# PCB_OnOnfre_SINGLE_BETA1_Solenoid.net
KiCad netlist of a schematic drawn in EAGLE
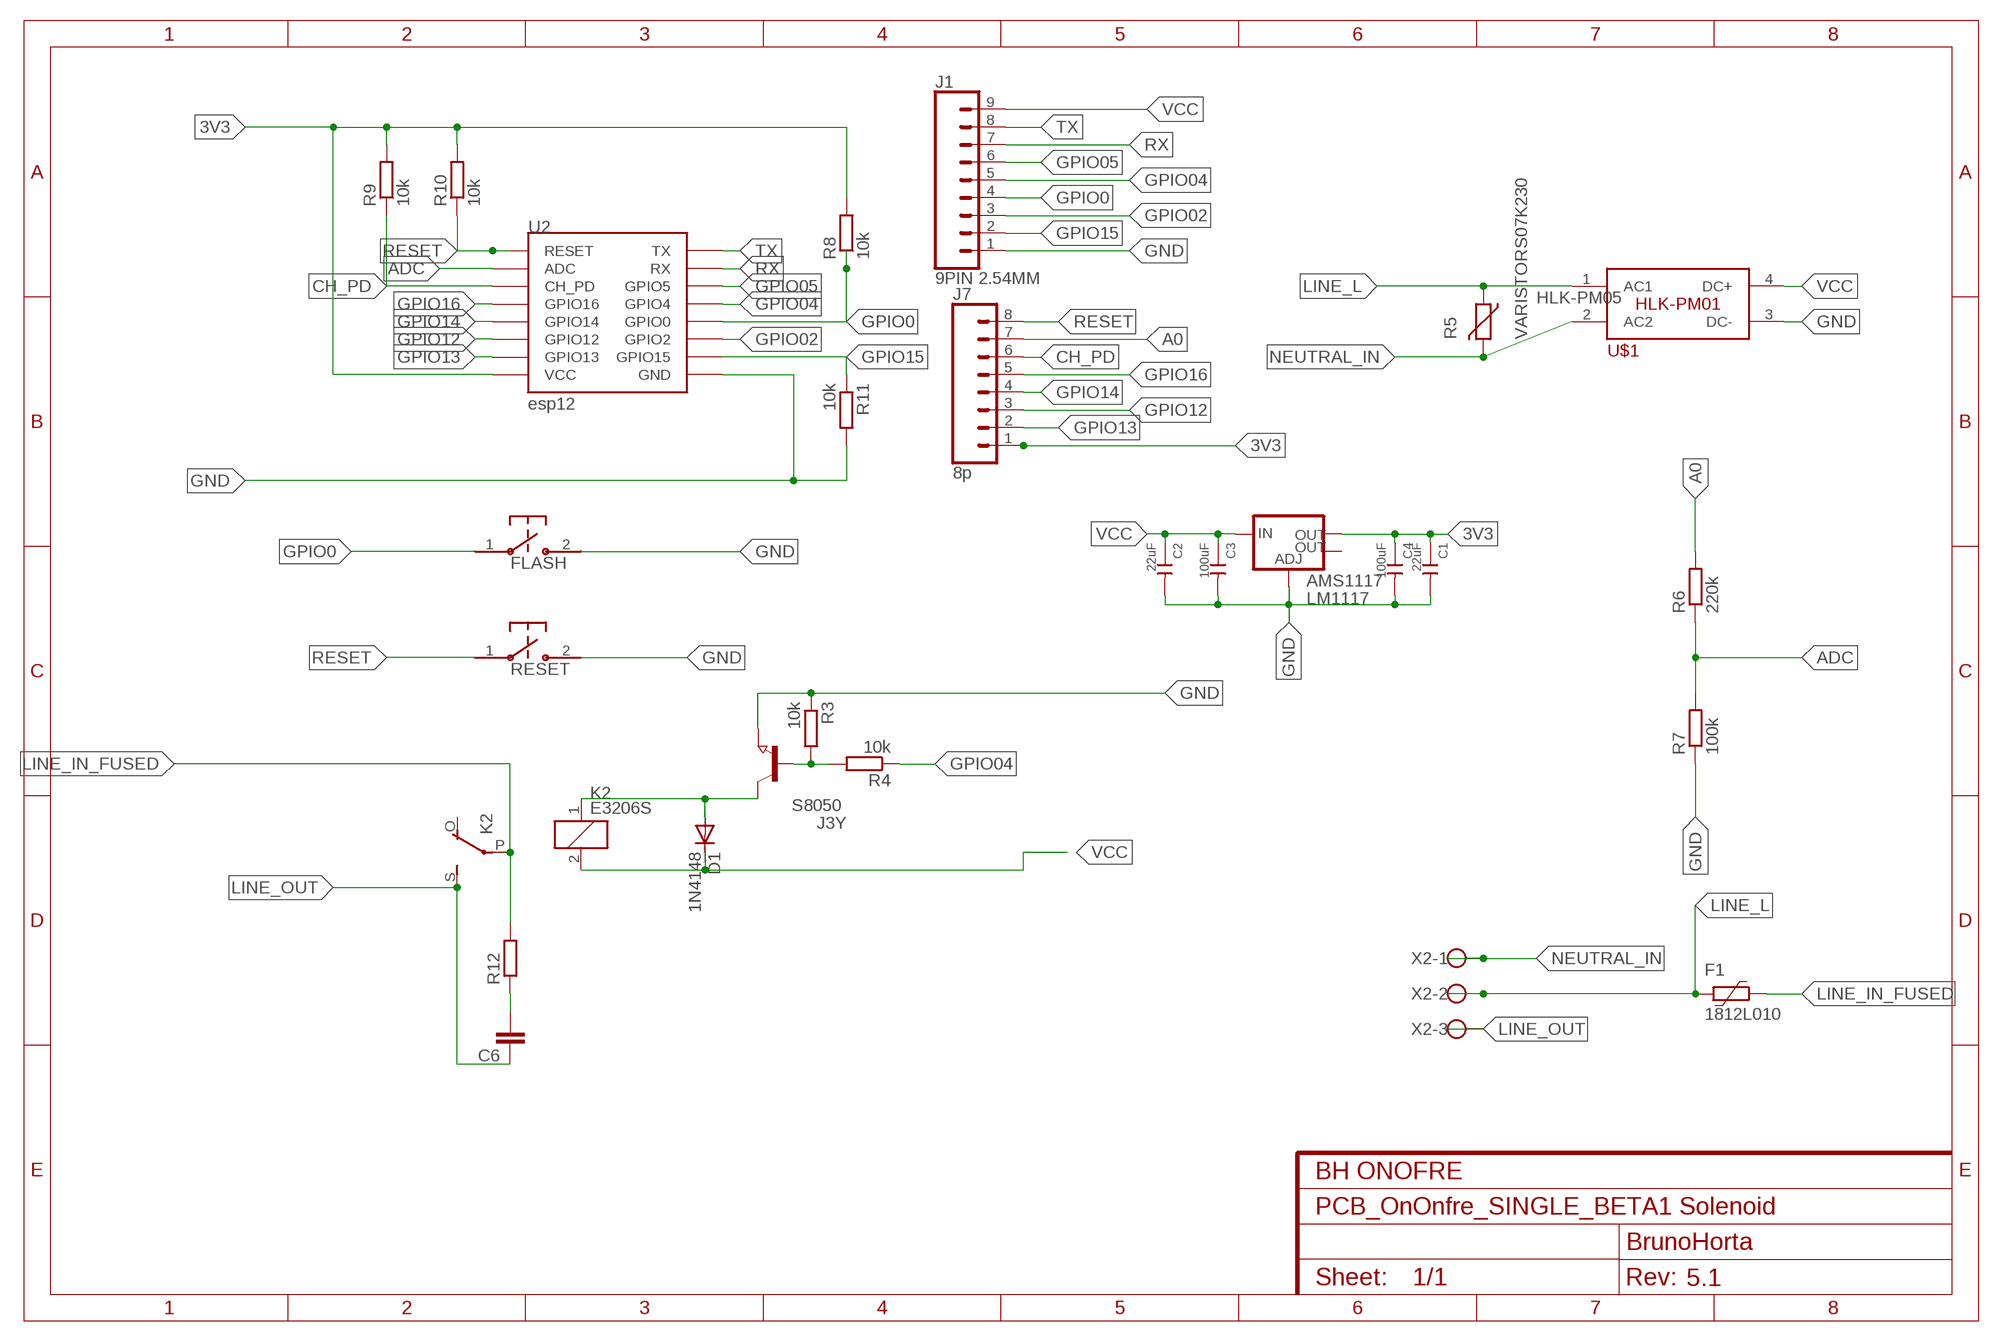
[diagram p0: schematic, sheet 1]

(export (version "E")
  (design (tool "Eeschema 10.0.6"))
  (components
    (comp (ref "AMS1117")
      (value "LM1117")
      (footprint "eagle-import:SOT223")
      (libsource (lib "eagle-import") (part "V_REG_LM1117SOT223"))
    )
    (comp (ref "C1")
      (value "22uF")
      (footprint "eagle-import:C1206")
      (fields (field (name "MPN") "CC1206KKX7RCBB102"))
      (libsource (lib "eagle-import") (part "CERAMIC-1NF-1KV-10%-X7R?(1206)"))
    )
    (comp (ref "C2")
      (value "22uF")
      (footprint "eagle-import:C1206")
      (fields (field (name "MPN") "CC1206KKX7RCBB102"))
      (libsource (lib "eagle-import") (part "CERAMIC-1NF-1KV-10%-X7R?(1206)"))
    )
    (comp (ref "C3")
      (value "100uF")
      (footprint "eagle-import:C1206")
      (fields (field (name "MPN") "CC1206KKX7RCBB102"))
      (libsource (lib "eagle-import") (part "CERAMIC-1NF-1KV-10%-X7R?(1206)"))
    )
    (comp (ref "C4")
      (value "100uF")
      (footprint "eagle-import:C1206")
      (fields (field (name "MPN") "CC1206KKX7RCBB102"))
      (libsource (lib "eagle-import") (part "CERAMIC-1NF-1KV-10%-X7R?(1206)"))
    )
    (comp (ref "C6")
      (value "C-EU102-043X133")
      (footprint "eagle-import:C102-043X133")
      (libsource (lib "eagle-import") (part "C-EU102-043X133"))
    )
    (comp (ref "D1")
      (value "1N4148")
      (footprint "eagle-import:SOD80C")
      (libsource (lib "eagle-import") (part "DIODE-SOD80C"))
    )
    (comp (ref "F1")
      (value "1812L010")
      (footprint "eagle-import:1812L")
      (fields (field (name "MF") "Littelfuse"))
      (libsource (lib "eagle-import") (part "?1812L010"))
    )
    (comp (ref "FLASH")
      (value "B3U-1000P-2P-SMD")
      (footprint "eagle-import:B3U-1000P")
      (fields (field (name "MANUFACTURER") "Omron") (field (name "MPN") "B3U-1000P"))
      (libsource (lib "eagle-import") (part "B3U-1000P"))
    )
    (comp (ref "J1")
      (value "9PIN 2.54MM")
      (footprint "eagle-import:1X09")
      (libsource (lib "eagle-import") (part "CONN_09"))
    )
    (comp (ref "J3Y")
      (value "S8050")
      (footprint "eagle-import:SOT23")
      (libsource (lib "eagle-import") (part "NPN-TRANSISTOR_SOT23"))
    )
    (comp (ref "J7")
      (value "8p")
      (footprint "eagle-import:1X08")
      (libsource (lib "eagle-import") (part "CONN_08{dblquote}"))
    )
    (comp (ref "K2")
      (value "E3206S")
      (footprint "eagle-import:E3206S")
      (libsource (lib "eagle-import") (part "E3206S"))
    )
    (comp (ref "R3")
      (value "10k")
      (footprint "eagle-import:R0603")
      (libsource (lib "eagle-import") (part "R-EU_R0603"))
    )
    (comp (ref "R4")
      (value "10k")
      (footprint "eagle-import:R0603")
      (libsource (lib "eagle-import") (part "R-EU_R0603"))
    )
    (comp (ref "R5")
      (value "VARISTORS07K230")
      (footprint "eagle-import:S07K230")
      (libsource (lib "eagle-import") (part "VARISTORS07K230"))
    )
    (comp (ref "R6")
      (value "220k")
      (footprint "eagle-import:R0603")
      (libsource (lib "eagle-import") (part "R-EU_R0603"))
    )
    (comp (ref "R7")
      (value "100k")
      (footprint "eagle-import:R0603")
      (libsource (lib "eagle-import") (part "R-EU_R0603"))
    )
    (comp (ref "R8")
      (value "10k")
      (footprint "eagle-import:R0603")
      (libsource (lib "eagle-import") (part "R-EU_R0603"))
    )
    (comp (ref "R9")
      (value "10k")
      (footprint "eagle-import:R0603")
      (libsource (lib "eagle-import") (part "R-EU_R0603"))
    )
    (comp (ref "R10")
      (value "10k")
      (footprint "eagle-import:R0603")
      (libsource (lib "eagle-import") (part "R-EU_R0603"))
    )
    (comp (ref "R11")
      (value "10k")
      (footprint "eagle-import:R0603")
      (libsource (lib "eagle-import") (part "R-EU_R0603"))
    )
    (comp (ref "R12")
      (value "R-EU_R2512")
      (footprint "eagle-import:R2512")
      (libsource (lib "eagle-import") (part "R-EU_R2512"))
    )
    (comp (ref "RESET")
      (value "B3U-1000P-2P-SMD")
      (footprint "eagle-import:B3U-1000P")
      (fields (field (name "MANUFACTURER") "Omron") (field (name "MPN") "B3U-1000P"))
      (libsource (lib "eagle-import") (part "B3U-1000P"))
    )
    (comp (ref "U$1")
      (value "HLK-PM01")
      (footprint "eagle-import:HLK-PM01")
      (fields (field (name "MF") "Hi-link") (field (name "MP") "hlk-pm01"))
      (libsource (lib "eagle-import") (part "HLK-PM01"))
    )
    (comp (ref "U2")
      (value "esp12")
      (footprint "eagle-import:ESP12-SMD")
      (libsource (lib "eagle-import") (part "ESP12SMD"))
    )
    (comp (ref "X2")
      (value "W237-103")
      (footprint "eagle-import:W237-103")
      (fields (field (name "MPN") "237-103"))
      (libsource (lib "eagle-import") (part "W237-103"))
    )
  )
  (nets
    (net (code "1") (name "3V3") (class "Default")
      (node (ref "AMS1117") (pin "2") (pinfunction "OUT_2") (pintype "output"))
      (node (ref "C1") (pin "1") (pinfunction "1_1") (pintype "passive"))
      (node (ref "C4") (pin "1") (pinfunction "1_1") (pintype "passive"))
      (node (ref "J7") (pin "1") (pinfunction "1_1") (pintype "passive"))
      (node (ref "R10") (pin "2") (pinfunction "2_2") (pintype "passive"))
      (node (ref "R8") (pin "2") (pinfunction "2_2") (pintype "passive"))
      (node (ref "R9") (pin "2") (pinfunction "2_2") (pintype "passive"))
      (node (ref "U2") (pin "VCC") (pinfunction "VCC_VCC") (pintype "bidirectional"))
    )
    (net (code "2") (name "A0") (class "Default")
      (node (ref "J7") (pin "7") (pinfunction "7_7") (pintype "passive"))
      (node (ref "R6") (pin "2") (pinfunction "2_2") (pintype "passive"))
    )
    (net (code "3") (name "ADC") (class "Default")
      (node (ref "R6") (pin "1") (pinfunction "1_1") (pintype "passive"))
      (node (ref "R7") (pin "2") (pinfunction "2_2") (pintype "passive"))
      (node (ref "U2") (pin "ADC") (pinfunction "ADC_ADC") (pintype "bidirectional"))
    )
    (net (code "4") (name "CH_PD") (class "Default")
      (node (ref "J7") (pin "6") (pinfunction "6_6") (pintype "passive"))
      (node (ref "R9") (pin "1") (pinfunction "1_1") (pintype "passive"))
      (node (ref "U2") (pin "CH_PD") (pinfunction "CH_PD_CH_PD") (pintype "bidirectional"))
    )
    (net (code "5") (name "GND") (class "Default")
      (node (ref "AMS1117") (pin "1") (pinfunction "ADJ_1") (pintype "input"))
      (node (ref "C1") (pin "2") (pinfunction "2_2") (pintype "passive"))
      (node (ref "C2") (pin "2") (pinfunction "2_2") (pintype "passive"))
      (node (ref "C3") (pin "2") (pinfunction "2_2") (pintype "passive"))
      (node (ref "C4") (pin "2") (pinfunction "2_2") (pintype "passive"))
      (node (ref "FLASH") (pin "2") (pinfunction "P$2_2") (pintype "passive"))
      (node (ref "J1") (pin "1") (pinfunction "1_1") (pintype "passive"))
      (node (ref "J3Y") (pin "2") (pinfunction "E_2") (pintype "passive"))
      (node (ref "R11") (pin "2") (pinfunction "2_2") (pintype "passive"))
      (node (ref "R3") (pin "1") (pinfunction "1_1") (pintype "passive"))
      (node (ref "R7") (pin "1") (pinfunction "1_1") (pintype "passive"))
      (node (ref "RESET") (pin "2") (pinfunction "P$2_2") (pintype "passive"))
      (node (ref "U$1") (pin "3") (pinfunction "DC-_3") (pintype "power_in"))
      (node (ref "U2") (pin "GND") (pinfunction "GND_GND") (pintype "bidirectional"))
    )
    (net (code "6") (name "GPIO0") (class "Default")
      (node (ref "FLASH") (pin "1") (pinfunction "P$1_1") (pintype "passive"))
      (node (ref "J1") (pin "4") (pinfunction "4_4") (pintype "passive"))
      (node (ref "R8") (pin "1") (pinfunction "1_1") (pintype "passive"))
      (node (ref "U2") (pin "GPIO0") (pinfunction "GPIO0_GPIO0") (pintype "bidirectional"))
    )
    (net (code "7") (name "GPIO02") (class "Default")
      (node (ref "J1") (pin "3") (pinfunction "3_3") (pintype "passive"))
      (node (ref "U2") (pin "GPIO2") (pinfunction "GPIO2_GPIO2") (pintype "bidirectional"))
    )
    (net (code "8") (name "GPIO04") (class "Default")
      (node (ref "J1") (pin "5") (pinfunction "5_5") (pintype "passive"))
      (node (ref "R4") (pin "1") (pinfunction "1_1") (pintype "passive"))
      (node (ref "U2") (pin "GPIO4") (pinfunction "GPIO4_GPIO4") (pintype "bidirectional"))
    )
    (net (code "9") (name "GPIO05") (class "Default")
      (node (ref "J1") (pin "6") (pinfunction "6_6") (pintype "passive"))
      (node (ref "U2") (pin "GPIO5") (pinfunction "GPIO5_GPIO5") (pintype "bidirectional"))
    )
    (net (code "10") (name "GPIO12") (class "Default")
      (node (ref "J7") (pin "3") (pinfunction "3_3") (pintype "passive"))
      (node (ref "U2") (pin "GPIO12") (pinfunction "GPIO12_GPIO12") (pintype "bidirectional"))
    )
    (net (code "11") (name "GPIO13") (class "Default")
      (node (ref "J7") (pin "2") (pinfunction "2_2") (pintype "passive"))
      (node (ref "U2") (pin "GPIO13") (pinfunction "GPIO13_GPIO13") (pintype "bidirectional"))
    )
    (net (code "12") (name "GPIO14") (class "Default")
      (node (ref "J7") (pin "4") (pinfunction "4_4") (pintype "passive"))
      (node (ref "U2") (pin "GPIO14") (pinfunction "GPIO14_GPIO14") (pintype "bidirectional"))
    )
    (net (code "13") (name "GPIO15") (class "Default")
      (node (ref "J1") (pin "2") (pinfunction "2_2") (pintype "passive"))
      (node (ref "R11") (pin "1") (pinfunction "1_1") (pintype "passive"))
      (node (ref "U2") (pin "GPIO15") (pinfunction "GPIO15_GPIO15") (pintype "bidirectional"))
    )
    (net (code "14") (name "GPIO16") (class "Default")
      (node (ref "J7") (pin "5") (pinfunction "5_5") (pintype "passive"))
      (node (ref "U2") (pin "GPIO16") (pinfunction "GPIO16_GPIO16") (pintype "bidirectional"))
    )
    (net (code "15") (name "LINE_IN_FUSED") (class "Default")
      (node (ref "F1") (pin "1") (pinfunction "1_1") (pintype "passive"))
      (node (ref "K2") (pin "P") (pinfunction "P_P") (pintype "passive"))
      (node (ref "R12") (pin "2") (pinfunction "2_2") (pintype "passive"))
    )
    (net (code "16") (name "LINE_L") (class "Default")
      (node (ref "F1") (pin "2") (pinfunction "2_2") (pintype "passive"))
      (node (ref "R5") (pin "1") (pinfunction "1_1") (pintype "passive"))
      (node (ref "U$1") (pin "1") (pinfunction "AC1_1") (pintype "power_in"))
      (node (ref "X2") (pin "2") (pinfunction "KL_2") (pintype "passive"))
    )
    (net (code "17") (name "LINE_OUT") (class "Default")
      (node (ref "C6") (pin "1") (pinfunction "1_1") (pintype "passive"))
      (node (ref "K2") (pin "S") (pinfunction "S_S") (pintype "passive"))
      (node (ref "X2") (pin "3") (pinfunction "KL_3") (pintype "passive"))
    )
    (net (code "18") (name "NEUTRAL_IN") (class "Default")
      (node (ref "R5") (pin "2") (pinfunction "2_2") (pintype "passive"))
      (node (ref "U$1") (pin "2") (pinfunction "AC2_2") (pintype "power_in"))
      (node (ref "X2") (pin "1") (pinfunction "KL_1") (pintype "passive"))
    )
    (net (code "19") (name "Net-(C6-Pad2)") (class "Default")
      (node (ref "C6") (pin "2") (pinfunction "2_2") (pintype "passive"))
      (node (ref "R12") (pin "1") (pinfunction "1_1") (pintype "passive"))
    )
    (net (code "20") (name "Net-(J3Y-B)") (class "Default")
      (node (ref "J3Y") (pin "1") (pinfunction "B_1") (pintype "passive"))
      (node (ref "R3") (pin "2") (pinfunction "2_2") (pintype "passive"))
      (node (ref "R4") (pin "2") (pinfunction "2_2") (pintype "passive"))
    )
    (net (code "21") (name "Net-(J3Y-C)") (class "Default")
      (node (ref "D1") (pin "A") (pinfunction "A_A") (pintype "passive"))
      (node (ref "J3Y") (pin "3") (pinfunction "C_3") (pintype "passive"))
      (node (ref "K2") (pin "1") (pinfunction "1_1") (pintype "passive"))
    )
    (net (code "22") (name "RESET") (class "Default")
      (node (ref "J7") (pin "8") (pinfunction "8_8") (pintype "passive"))
      (node (ref "R10") (pin "1") (pinfunction "1_1") (pintype "passive"))
      (node (ref "RESET") (pin "1") (pinfunction "P$1_1") (pintype "passive"))
      (node (ref "U2") (pin "RESET") (pinfunction "RESET_RESET") (pintype "bidirectional"))
    )
    (net (code "23") (name "RX") (class "Default")
      (node (ref "J1") (pin "7") (pinfunction "7_7") (pintype "passive"))
      (node (ref "U2") (pin "RXD0") (pinfunction "RX_RXD0") (pintype "bidirectional"))
    )
    (net (code "24") (name "TX") (class "Default")
      (node (ref "J1") (pin "8") (pinfunction "8_8") (pintype "passive"))
      (node (ref "U2") (pin "TXD0") (pinfunction "TX_TXD0") (pintype "bidirectional"))
    )
    (net (code "25") (name "VCC") (class "Default")
      (node (ref "AMS1117") (pin "3") (pinfunction "IN_3") (pintype "input"))
      (node (ref "C2") (pin "1") (pinfunction "1_1") (pintype "passive"))
      (node (ref "C3") (pin "1") (pinfunction "1_1") (pintype "passive"))
      (node (ref "D1") (pin "C") (pinfunction "C_C") (pintype "passive"))
      (node (ref "J1") (pin "9") (pinfunction "9_9") (pintype "passive"))
      (node (ref "K2") (pin "2") (pinfunction "2_2") (pintype "passive"))
      (node (ref "U$1") (pin "4") (pinfunction "DC+_4") (pintype "power_in"))
    )
    (net (code "26") (name "unconnected-(AMS1117-OUT-Pad4)") (class "Default")
      (node (ref "AMS1117") (pin "4") (pinfunction "OUT_4") (pintype "output"))
    )
    (net (code "27") (name "unconnected-(K2-PadO)") (class "Default")
      (node (ref "K2") (pin "O") (pinfunction "O_O") (pintype "passive"))
    )
  )
)
